# Schema.net
KiCad netlist of a schematic drawn in Altium Designer
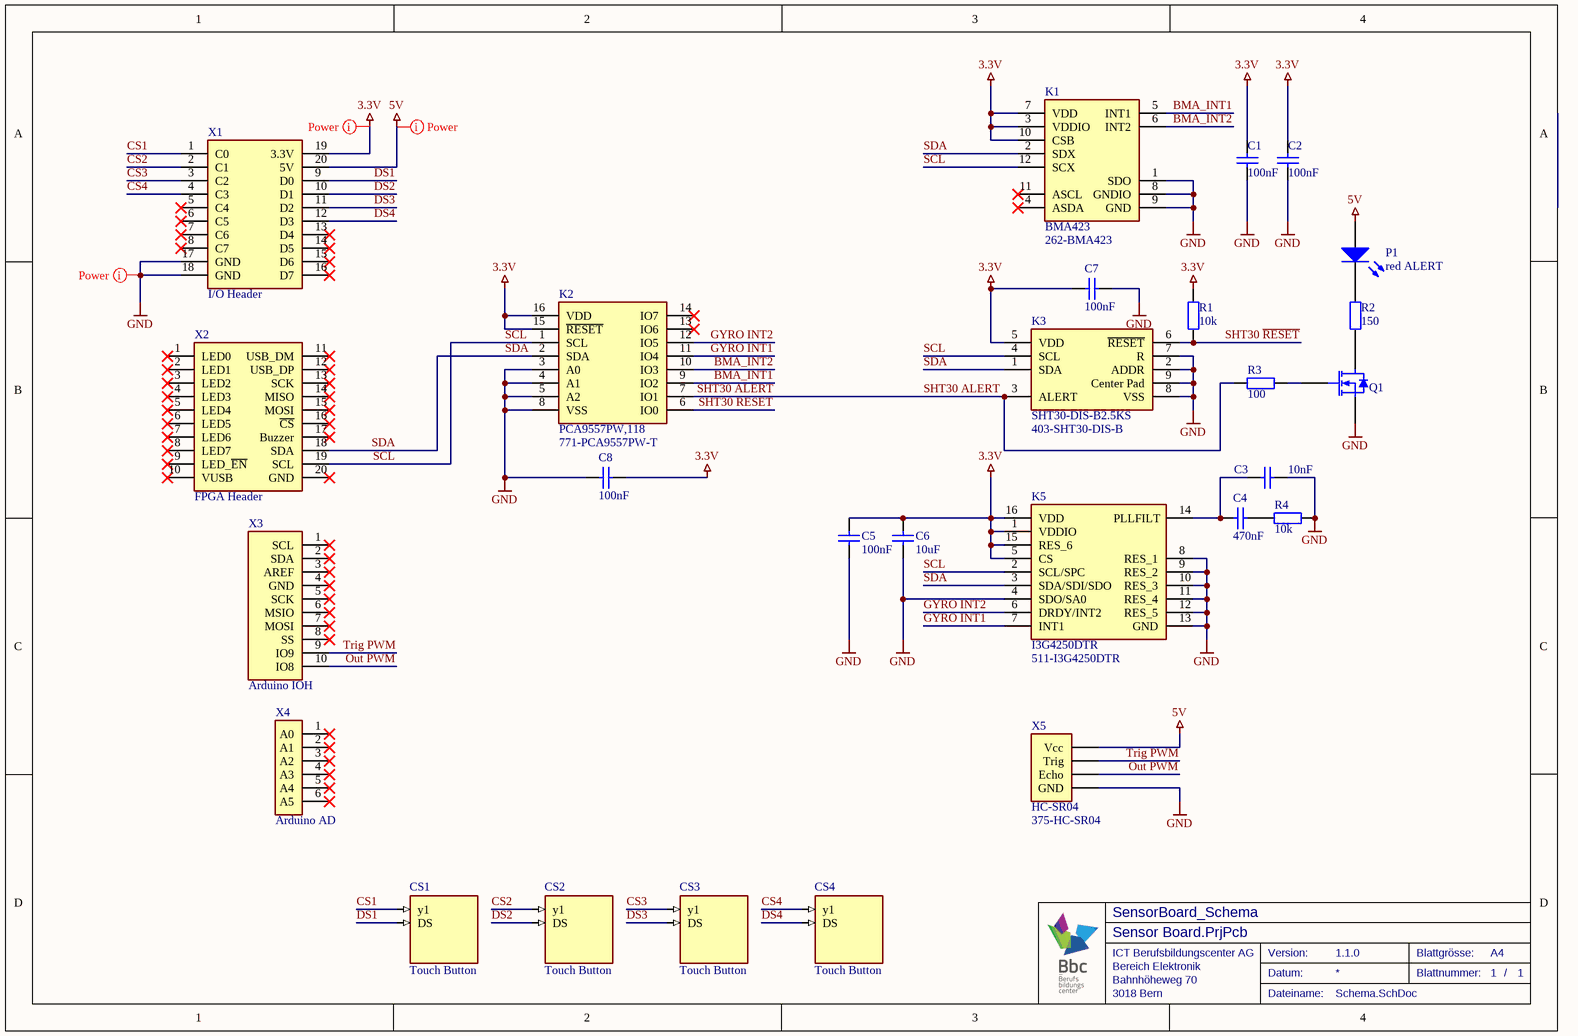
[diagram p0: Schema.SchDoc]

(export (version "E")
  (design (tool "Eeschema 10.0.6"))
  (components
    (comp (ref "C1")
      (value "100nF")
      (footprint "CAP CER 0805 H")
      (description "Non polarized capacitor")
      (fields (field (name "Comment") "Capacitor") (field (name "PUBLISHER") "ICT Berufsbildungscenter AG"))
      (libsource (lib "BBC_Components") (part "Capacitor"))
    )
    (comp (ref "C2")
      (value "100nF")
      (footprint "CAP CER 0805 H")
      (description "Non polarized capacitor")
      (fields (field (name "Comment") "Capacitor") (field (name "PUBLISHER") "ICT Berufsbildungscenter AG"))
      (libsource (lib "BBC_Components") (part "Capacitor"))
    )
    (comp (ref "C3")
      (value "10nF")
      (footprint "CAP CER 0805 H")
      (description "Non polarized capacitor")
      (fields (field (name "Comment") "Capacitor") (field (name "PUBLISHER") "ICT Berufsbildungscenter AG"))
      (libsource (lib "BBC_Components") (part "Capacitor"))
    )
    (comp (ref "C4")
      (value "470nF")
      (footprint "CAP CER 0805 H")
      (description "Non polarized capacitor")
      (fields (field (name "Comment") "Capacitor") (field (name "PUBLISHER") "ICT Berufsbildungscenter AG"))
      (libsource (lib "BBC_Components") (part "Capacitor"))
    )
    (comp (ref "C5")
      (value "100nF")
      (footprint "CAP CER 0805 H")
      (description "Non polarized capacitor")
      (fields (field (name "Comment") "Capacitor") (field (name "PUBLISHER") "ICT Berufsbildungscenter AG"))
      (libsource (lib "BBC_Components") (part "Capacitor"))
    )
    (comp (ref "C6")
      (value "10uF")
      (footprint "CAP CER 0805 H")
      (description "Non polarized capacitor")
      (fields (field (name "Comment") "Capacitor") (field (name "PUBLISHER") "ICT Berufsbildungscenter AG"))
      (libsource (lib "BBC_Components") (part "Capacitor"))
    )
    (comp (ref "C7")
      (value "100nF")
      (footprint "CAP CER 0805 H")
      (description "Non polarized capacitor")
      (fields (field (name "Comment") "Capacitor") (field (name "PUBLISHER") "ICT Berufsbildungscenter AG"))
      (libsource (lib "BBC_Components") (part "Capacitor"))
    )
    (comp (ref "C8")
      (value "100nF")
      (footprint "CAP CER 0805 H")
      (description "Non polarized capacitor")
      (fields (field (name "Comment") "Capacitor") (field (name "PUBLISHER") "ICT Berufsbildungscenter AG"))
      (libsource (lib "BBC_Components") (part "Capacitor"))
    )
    (comp (ref "CS1")
      (value "Touch Button")
      (footprint "Button Self Rectangle")
      (description "Rechteckige Kupferfläche")
      (libsource (lib "SchematicLibrary") (part "Touch Button"))
    )
    (comp (ref "CS2")
      (value "Touch Button")
      (footprint "Button Self Rectangle")
      (description "Rechteckige Kupferfläche")
      (libsource (lib "SchematicLibrary") (part "Touch Button"))
    )
    (comp (ref "CS3")
      (value "Touch Button")
      (footprint "Button Self Rectangle")
      (description "Rechteckige Kupferfläche")
      (libsource (lib "SchematicLibrary") (part "Touch Button"))
    )
    (comp (ref "CS4")
      (value "Touch Button")
      (footprint "Button Self Rectangle")
      (description "Rechteckige Kupferfläche")
      (libsource (lib "SchematicLibrary") (part "Touch Button"))
    )
    (comp (ref "K1")
      (value "BMA423")
      (footprint "Footprints:BMA423")
      (description "Beschleunigungsmesser Triaxial low-g 12bit Acceleration Sensor")
      (fields (field (name "SUPPLIER PART NUMBER 1") "262-BMA423"))
      (libsource (lib "SchematicLibrary") (part "Beschleunigungsmesser"))
    )
    (comp (ref "K2")
      (value "PCA9557PW,118")
      (footprint "Footprints:SOP65P640X110-16N")
      (description "Schnittstelle - I/O-Erweiterer OCT SMBUS/I2C INTRFC")
      (fields (field (name "SUPPLIER PART NUMBER 1") "771-PCA9557PW-T"))
      (libsource (lib "SchematicLibrary") (part "Port Expander"))
    )
    (comp (ref "K3")
      (value "SHT30-DIS-B2.5KS")
      (footprint "Footprints:SHT30DISB25KS")
      (description "Feuchtigkeitssensoren für Plattenmontage RH Accuracy +/- 3% Digital, DFN Type")
      (fields (field (name "SUPPLIER PART NUMBER 1") "403-SHT30-DIS-B"))
      (libsource (lib "SchematicLibrary") (part "Humidity & Temp. Sensor"))
    )
    (comp (ref "K5")
      (value "I3G4250DTR")
      (footprint "Footprints:LGA-16L(4X4X1.1MM)")
      (description "Gyroskope AUTO & INDUSTRIAL SENSORS")
      (fields (field (name "SUPPLIER PART NUMBER 1") "511-I3G4250DTR"))
      (libsource (lib "SchematicLibrary") (part "Gyroskop"))
    )
    (comp (ref "P1")
      (value "red ALERT")
      (footprint "LED 1206 red H")
      (description "Light emitting diode")
      (fields (field (name "PUBLISHER") "ICT Berufsbildungscenter AG"))
      (libsource (lib "BBC_Components") (part "LED"))
    )
    (comp (ref "Q1")
      (value "MOSFET N-Channel")
      (footprint "SOT96P237X111-3N")
      (libsource (lib "SchematicLibrary") (part "MOSFET N-Channel"))
    )
    (comp (ref "R1")
      (value "10k")
      (footprint "RES 0805 H")
      (description "Resistor")
      (fields (field (name "PUBLISHER") "ICT Berufsbildungscenter AG"))
      (libsource (lib "") (part "Resistor_1"))
    )
    (comp (ref "R2")
      (value "150")
      (footprint "RES 0805 H")
      (description "Resistor")
      (fields (field (name "PUBLISHER") "ICT Berufsbildungscenter AG"))
      (libsource (lib "") (part "Resistor_1"))
    )
    (comp (ref "R3")
      (value "100")
      (footprint "RES 0805 H")
      (description "Resistor")
      (fields (field (name "PUBLISHER") "ICT Berufsbildungscenter AG"))
      (libsource (lib "BBC_Components") (part "Resistor"))
    )
    (comp (ref "R4")
      (value "10k")
      (footprint "RES 0805 H")
      (description "Resistor")
      (fields (field (name "PUBLISHER") "ICT Berufsbildungscenter AG"))
      (libsource (lib "BBC_Components") (part "Resistor"))
    )
    (comp (ref "X1")
      (value "I/O Header")
      (footprint "Header THT male 2x10")
      (description "board to board header")
      (fields (field (name "PUBLISHER") "ICT Berufsbildungscenter AG"))
      (libsource (lib "SchematicLibrary") (part "I/O Header"))
    )
    (comp (ref "X2")
      (value "FPGA Header")
      (footprint "Header THT male 2x10")
      (description "board to board header")
      (fields (field (name "PUBLISHER") "ICT Berufsbildungscenter AG"))
      (libsource (lib "SchematicLibrary") (part "FPGA Header"))
    )
    (comp (ref "X3")
      (value "Arduino IOH")
      (footprint "Header THT male 1x10")
      (description "board to board header")
      (fields (field (name "PUBLISHER") "ICT Berufsbildungscenter AG"))
      (libsource (lib "SchematicLibrary") (part "Arduino IOH"))
    )
    (comp (ref "X4")
      (value "Arduino AD")
      (footprint "Header THT male 1x6")
      (description "board to board header")
      (fields (field (name "PUBLISHER") "ICT Berufsbildungscenter AG"))
      (libsource (lib "SchematicLibrary") (part "Arduino AD"))
    )
    (comp (ref "X5")
      (value "HC-SR04")
      (footprint "HC-SR04")
      (description "Buchsenanschluss für den Sensor")
      (fields (field (name "SUPPLIER PART NUMBER 1") "375-HC-SR04"))
      (libsource (lib "SchematicLibrary") (part "Ultraschall-Distanzsensor"))
    )
  )
  (nets
    (net (code "1") (name "/BMA_INT1") (class "Default")
      (node (ref "K1") (pin "5") (pinfunction "INT1_5") (pintype "passive"))
      (node (ref "K2") (pin "9") (pinfunction "IO2_9") (pintype "passive"))
    )
    (net (code "2") (name "/BMA_INT2") (class "Default")
      (node (ref "K1") (pin "6") (pinfunction "INT2_6") (pintype "passive"))
      (node (ref "K2") (pin "10") (pinfunction "IO3_10") (pintype "passive"))
    )
    (net (code "3") (name "/CS1") (class "Default")
      (node (ref "CS1") (pin "y1") (pinfunction "y1_y1") (pintype "input"))
      (node (ref "X1") (pin "1") (pinfunction "C0_1") (pintype "passive"))
    )
    (net (code "4") (name "/CS2") (class "Default")
      (node (ref "CS2") (pin "y1") (pinfunction "y1_y1") (pintype "input"))
      (node (ref "X1") (pin "2") (pinfunction "C1_2") (pintype "passive"))
    )
    (net (code "5") (name "/CS3") (class "Default")
      (node (ref "CS3") (pin "y1") (pinfunction "y1_y1") (pintype "input"))
      (node (ref "X1") (pin "3") (pinfunction "C2_3") (pintype "passive"))
    )
    (net (code "6") (name "/CS4") (class "Default")
      (node (ref "CS4") (pin "y1") (pinfunction "y1_y1") (pintype "input"))
      (node (ref "X1") (pin "4") (pinfunction "C3_4") (pintype "passive"))
    )
    (net (code "7") (name "/DS1") (class "Default")
      (node (ref "CS1") (pin "DS") (pinfunction "DS_DS") (pintype "input"))
      (node (ref "X1") (pin "9") (pinfunction "D0_9") (pintype "passive"))
    )
    (net (code "8") (name "/DS2") (class "Default")
      (node (ref "CS2") (pin "DS") (pinfunction "DS_DS") (pintype "input"))
      (node (ref "X1") (pin "10") (pinfunction "D1_10") (pintype "passive"))
    )
    (net (code "9") (name "/DS3") (class "Default")
      (node (ref "CS3") (pin "DS") (pinfunction "DS_DS") (pintype "input"))
      (node (ref "X1") (pin "11") (pinfunction "D2_11") (pintype "passive"))
    )
    (net (code "10") (name "/DS4") (class "Default")
      (node (ref "CS4") (pin "DS") (pinfunction "DS_DS") (pintype "input"))
      (node (ref "X1") (pin "12") (pinfunction "D3_12") (pintype "passive"))
    )
    (net (code "11") (name "/GYRO INT1") (class "Default")
      (node (ref "K2") (pin "11") (pinfunction "IO4_11") (pintype "passive"))
      (node (ref "K5") (pin "7") (pinfunction "INT1_7") (pintype "passive"))
    )
    (net (code "12") (name "/GYRO INT2") (class "Default")
      (node (ref "K2") (pin "12") (pinfunction "IO5_12") (pintype "passive"))
      (node (ref "K5") (pin "6") (pinfunction "DRDY/INT2_6") (pintype "passive"))
    )
    (net (code "13") (name "/Out PWM") (class "Default")
      (node (ref "X3") (pin "10") (pinfunction "IO8_10") (pintype "passive"))
      (node (ref "X5") (pin "3") (pinfunction "Echo_3") (pintype "passive"))
    )
    (net (code "14") (name "/SCL") (class "Default")
      (node (ref "K1") (pin "12") (pinfunction "SCX_12") (pintype "passive"))
      (node (ref "K2") (pin "1") (pinfunction "SCL_1") (pintype "passive"))
      (node (ref "K3") (pin "4") (pinfunction "SCL_4") (pintype "passive"))
      (node (ref "K5") (pin "2") (pinfunction "SCL/SPC_2") (pintype "passive"))
      (node (ref "X2") (pin "19") (pinfunction "SCL_19") (pintype "passive"))
    )
    (net (code "15") (name "/SDA") (class "Default")
      (node (ref "K1") (pin "2") (pinfunction "SDX_2") (pintype "passive"))
      (node (ref "K2") (pin "2") (pinfunction "SDA_2") (pintype "passive"))
      (node (ref "K3") (pin "1") (pinfunction "SDA_1") (pintype "passive"))
      (node (ref "K5") (pin "3") (pinfunction "SDA/SDI/SDO_3") (pintype "passive"))
      (node (ref "X2") (pin "18") (pinfunction "SDA_18") (pintype "passive"))
    )
    (net (code "16") (name "/SHT30 ALERT") (class "Default")
      (node (ref "K2") (pin "7") (pinfunction "IO1_7") (pintype "passive"))
      (node (ref "K3") (pin "3") (pinfunction "ALERT_3") (pintype "passive"))
      (node (ref "R3") (pin "1") (pinfunction "1_1") (pintype "passive"))
    )
    (net (code "17") (name "/SHT30 ~{RESET}") (class "Default")
      (node (ref "K2") (pin "6") (pinfunction "IO0_6") (pintype "passive"))
      (node (ref "K3") (pin "6") (pinfunction "~{RESET}_6") (pintype "passive"))
      (node (ref "R1") (pin "1") (pinfunction "1_1") (pintype "passive"))
    )
    (net (code "18") (name "/Trig PWM") (class "Default")
      (node (ref "X3") (pin "9") (pinfunction "IO9_9") (pintype "passive"))
      (node (ref "X5") (pin "2") (pinfunction "Trig_2") (pintype "passive"))
    )
    (net (code "19") (name "3.3V") (class "Default")
      (node (ref "C1") (pin "2") (pinfunction "2_2") (pintype "passive"))
      (node (ref "C2") (pin "1") (pinfunction "1_1") (pintype "passive"))
      (node (ref "C5") (pin "1") (pinfunction "1_1") (pintype "passive"))
      (node (ref "C6") (pin "1") (pinfunction "1_1") (pintype "passive"))
      (node (ref "C7") (pin "1") (pinfunction "1_1") (pintype "passive"))
      (node (ref "C8") (pin "2") (pinfunction "2_2") (pintype "passive"))
      (node (ref "K1") (pin "10") (pinfunction "CSB_10") (pintype "passive"))
      (node (ref "K1") (pin "3") (pinfunction "VDDIO_3") (pintype "passive"))
      (node (ref "K1") (pin "7") (pinfunction "VDD_7") (pintype "passive"))
      (node (ref "K2") (pin "15") (pinfunction "~{RESET}_15") (pintype "passive"))
      (node (ref "K2") (pin "16") (pinfunction "VDD_16") (pintype "passive"))
      (node (ref "K3") (pin "5") (pinfunction "VDD_5") (pintype "passive"))
      (node (ref "K5") (pin "1") (pinfunction "VDDIO_1") (pintype "passive"))
      (node (ref "K5") (pin "15") (pinfunction "RES_6_15") (pintype "passive"))
      (node (ref "K5") (pin "16") (pinfunction "VDD_16") (pintype "passive"))
      (node (ref "K5") (pin "5") (pinfunction "CS_5") (pintype "passive"))
      (node (ref "R1") (pin "2") (pinfunction "2_2") (pintype "passive"))
      (node (ref "X1") (pin "19") (pinfunction "3.3V_19") (pintype "passive"))
    )
    (net (code "20") (name "5V") (class "Default")
      (node (ref "P1") (pin "A") (pinfunction "Anode_A") (pintype "passive"))
      (node (ref "X1") (pin "20") (pinfunction "5V_20") (pintype "passive"))
      (node (ref "X5") (pin "1") (pinfunction "Vcc_1") (pintype "passive"))
    )
    (net (code "21") (name "GND") (class "Default")
      (node (ref "C1") (pin "1") (pinfunction "1_1") (pintype "passive"))
      (node (ref "C2") (pin "2") (pinfunction "2_2") (pintype "passive"))
      (node (ref "C3") (pin "2") (pinfunction "2_2") (pintype "passive"))
      (node (ref "C5") (pin "2") (pinfunction "2_2") (pintype "passive"))
      (node (ref "C6") (pin "2") (pinfunction "2_2") (pintype "passive"))
      (node (ref "C7") (pin "2") (pinfunction "2_2") (pintype "passive"))
      (node (ref "C8") (pin "1") (pinfunction "1_1") (pintype "passive"))
      (node (ref "K1") (pin "1") (pinfunction "SDO_1") (pintype "passive"))
      (node (ref "K1") (pin "8") (pinfunction "GNDIO_8") (pintype "passive"))
      (node (ref "K1") (pin "9") (pinfunction "GND_9") (pintype "passive"))
      (node (ref "K2") (pin "3") (pinfunction "A0_3") (pintype "passive"))
      (node (ref "K2") (pin "4") (pinfunction "A1_4") (pintype "passive"))
      (node (ref "K2") (pin "5") (pinfunction "A2_5") (pintype "passive"))
      (node (ref "K2") (pin "8") (pinfunction "VSS_8") (pintype "passive"))
      (node (ref "K3") (pin "2") (pinfunction "ADDR_2") (pintype "passive"))
      (node (ref "K3") (pin "7") (pinfunction "R_7") (pintype "passive"))
      (node (ref "K3") (pin "8") (pinfunction "VSS_8") (pintype "passive"))
      (node (ref "K3") (pin "9") (pinfunction "Center_Pad_9") (pintype "passive"))
      (node (ref "K5") (pin "10") (pinfunction "RES_3_10") (pintype "passive"))
      (node (ref "K5") (pin "11") (pinfunction "RES_4_11") (pintype "passive"))
      (node (ref "K5") (pin "12") (pinfunction "RES_5_12") (pintype "passive"))
      (node (ref "K5") (pin "13") (pinfunction "GND_13") (pintype "passive"))
      (node (ref "K5") (pin "4") (pinfunction "SDO/SA0_4") (pintype "passive"))
      (node (ref "K5") (pin "8") (pinfunction "RES_1_8") (pintype "passive"))
      (node (ref "K5") (pin "9") (pinfunction "RES_2_9") (pintype "passive"))
      (node (ref "Q1") (pin "2") (pinfunction "S_2") (pintype "passive"))
      (node (ref "R4") (pin "2") (pinfunction "2_2") (pintype "passive"))
      (node (ref "X1") (pin "17") (pinfunction "GND_17") (pintype "passive"))
      (node (ref "X1") (pin "18") (pinfunction "GND_18") (pintype "passive"))
      (node (ref "X5") (pin "4") (pinfunction "GND_4") (pintype "passive"))
    )
    (net (code "22") (name "Net-(C4-Pad2)") (class "Default")
      (node (ref "C4") (pin "2") (pinfunction "2_2") (pintype "passive"))
      (node (ref "R4") (pin "1") (pinfunction "1_1") (pintype "passive"))
    )
    (net (code "23") (name "Net-(K5-PLLFILT)") (class "Default")
      (node (ref "C3") (pin "1") (pinfunction "1_1") (pintype "passive"))
      (node (ref "C4") (pin "1") (pinfunction "1_1") (pintype "passive"))
      (node (ref "K5") (pin "14") (pinfunction "PLLFILT_14") (pintype "passive"))
    )
    (net (code "24") (name "Net-(P1-Cathode)") (class "Default")
      (node (ref "P1") (pin "C") (pinfunction "Cathode_C") (pintype "passive"))
      (node (ref "R2") (pin "2") (pinfunction "2_2") (pintype "passive"))
    )
    (net (code "25") (name "Net-(Q1-D)") (class "Default")
      (node (ref "Q1") (pin "3") (pinfunction "D_3") (pintype "passive"))
      (node (ref "R2") (pin "1") (pinfunction "1_1") (pintype "passive"))
    )
    (net (code "26") (name "Net-(Q1-G)") (class "Default")
      (node (ref "Q1") (pin "1") (pinfunction "G_1") (pintype "passive"))
      (node (ref "R3") (pin "2") (pinfunction "2_2") (pintype "passive"))
    )
    (net (code "27") (name "unconnected-(K1-ASCL-Pad11)") (class "Default")
      (node (ref "K1") (pin "11") (pinfunction "ASCL_11") (pintype "passive+no_connect"))
    )
    (net (code "28") (name "unconnected-(K1-ASDA-Pad4)") (class "Default")
      (node (ref "K1") (pin "4") (pinfunction "ASDA_4") (pintype "passive+no_connect"))
    )
    (net (code "29") (name "unconnected-(K2-IO6-Pad13)") (class "Default")
      (node (ref "K2") (pin "13") (pinfunction "IO6_13") (pintype "passive+no_connect"))
    )
    (net (code "30") (name "unconnected-(K2-IO7-Pad14)") (class "Default")
      (node (ref "K2") (pin "14") (pinfunction "IO7_14") (pintype "passive+no_connect"))
    )
    (net (code "31") (name "unconnected-(X1-C4-Pad5)") (class "Default")
      (node (ref "X1") (pin "5") (pinfunction "C4_5") (pintype "passive+no_connect"))
    )
    (net (code "32") (name "unconnected-(X1-C5-Pad6)") (class "Default")
      (node (ref "X1") (pin "6") (pinfunction "C5_6") (pintype "passive+no_connect"))
    )
    (net (code "33") (name "unconnected-(X1-C6-Pad7)") (class "Default")
      (node (ref "X1") (pin "7") (pinfunction "C6_7") (pintype "passive+no_connect"))
    )
    (net (code "34") (name "unconnected-(X1-C7-Pad8)") (class "Default")
      (node (ref "X1") (pin "8") (pinfunction "C7_8") (pintype "passive+no_connect"))
    )
    (net (code "35") (name "unconnected-(X1-D4-Pad13)") (class "Default")
      (node (ref "X1") (pin "13") (pinfunction "D4_13") (pintype "passive+no_connect"))
    )
    (net (code "36") (name "unconnected-(X1-D5-Pad14)") (class "Default")
      (node (ref "X1") (pin "14") (pinfunction "D5_14") (pintype "passive+no_connect"))
    )
    (net (code "37") (name "unconnected-(X1-D6-Pad15)") (class "Default")
      (node (ref "X1") (pin "15") (pinfunction "D6_15") (pintype "passive+no_connect"))
    )
    (net (code "38") (name "unconnected-(X1-D7-Pad16)") (class "Default")
      (node (ref "X1") (pin "16") (pinfunction "D7_16") (pintype "passive+no_connect"))
    )
    (net (code "39") (name "unconnected-(X2-Buzzer-Pad17)") (class "Default")
      (node (ref "X2") (pin "17") (pinfunction "Buzzer_17") (pintype "passive+no_connect"))
    )
    (net (code "40") (name "unconnected-(X2-GND-Pad20)") (class "Default")
      (node (ref "X2") (pin "20") (pinfunction "GND_20") (pintype "passive+no_connect"))
    )
    (net (code "41") (name "unconnected-(X2-LED0-Pad1)") (class "Default")
      (node (ref "X2") (pin "1") (pinfunction "LED0_1") (pintype "passive+no_connect"))
    )
    (net (code "42") (name "unconnected-(X2-LED1-Pad2)") (class "Default")
      (node (ref "X2") (pin "2") (pinfunction "LED1_2") (pintype "passive+no_connect"))
    )
    (net (code "43") (name "unconnected-(X2-LED2-Pad3)") (class "Default")
      (node (ref "X2") (pin "3") (pinfunction "LED2_3") (pintype "passive+no_connect"))
    )
    (net (code "44") (name "unconnected-(X2-LED3-Pad4)") (class "Default")
      (node (ref "X2") (pin "4") (pinfunction "LED3_4") (pintype "passive+no_connect"))
    )
    (net (code "45") (name "unconnected-(X2-LED4-Pad5)") (class "Default")
      (node (ref "X2") (pin "5") (pinfunction "LED4_5") (pintype "passive+no_connect"))
    )
    (net (code "46") (name "unconnected-(X2-LED5-Pad6)") (class "Default")
      (node (ref "X2") (pin "6") (pinfunction "LED5_6") (pintype "passive+no_connect"))
    )
    (net (code "47") (name "unconnected-(X2-LED6-Pad7)") (class "Default")
      (node (ref "X2") (pin "7") (pinfunction "LED6_7") (pintype "passive+no_connect"))
    )
    (net (code "48") (name "unconnected-(X2-LED7-Pad8)") (class "Default")
      (node (ref "X2") (pin "8") (pinfunction "LED7_8") (pintype "passive+no_connect"))
    )
    (net (code "49") (name "unconnected-(X2-LED_~{EN}-Pad9)") (class "Default")
      (node (ref "X2") (pin "9") (pinfunction "LED_~{EN}_9") (pintype "passive+no_connect"))
    )
    (net (code "50") (name "unconnected-(X2-MISO-Pad14)") (class "Default")
      (node (ref "X2") (pin "14") (pinfunction "MISO_14") (pintype "passive+no_connect"))
    )
    (net (code "51") (name "unconnected-(X2-MOSI-Pad15)") (class "Default")
      (node (ref "X2") (pin "15") (pinfunction "MOSI_15") (pintype "passive+no_connect"))
    )
    (net (code "52") (name "unconnected-(X2-SCK-Pad13)") (class "Default")
      (node (ref "X2") (pin "13") (pinfunction "SCK_13") (pintype "passive+no_connect"))
    )
    (net (code "53") (name "unconnected-(X2-USB_DM-Pad11)") (class "Default")
      (node (ref "X2") (pin "11") (pinfunction "USB_DM_11") (pintype "passive+no_connect"))
    )
    (net (code "54") (name "unconnected-(X2-USB_DP-Pad12)") (class "Default")
      (node (ref "X2") (pin "12") (pinfunction "USB_DP_12") (pintype "passive+no_connect"))
    )
    (net (code "55") (name "unconnected-(X2-VUSB-Pad10)") (class "Default")
      (node (ref "X2") (pin "10") (pinfunction "VUSB_10") (pintype "passive+no_connect"))
    )
    (net (code "56") (name "unconnected-(X2-~{CS}-Pad16)") (class "Default")
      (node (ref "X2") (pin "16") (pinfunction "~{CS}_16") (pintype "passive+no_connect"))
    )
    (net (code "57") (name "unconnected-(X3-AREF-Pad3)") (class "Default")
      (node (ref "X3") (pin "3") (pinfunction "AREF_3") (pintype "passive+no_connect"))
    )
    (net (code "58") (name "unconnected-(X3-GND-Pad4)") (class "Default")
      (node (ref "X3") (pin "4") (pinfunction "GND_4") (pintype "passive+no_connect"))
    )
    (net (code "59") (name "unconnected-(X3-MOSI-Pad7)") (class "Default")
      (node (ref "X3") (pin "7") (pinfunction "MOSI_7") (pintype "passive+no_connect"))
    )
    (net (code "60") (name "unconnected-(X3-MSIO-Pad6)") (class "Default")
      (node (ref "X3") (pin "6") (pinfunction "MSIO_6") (pintype "passive+no_connect"))
    )
    (net (code "61") (name "unconnected-(X3-SCK-Pad5)") (class "Default")
      (node (ref "X3") (pin "5") (pinfunction "SCK_5") (pintype "passive+no_connect"))
    )
    (net (code "62") (name "unconnected-(X3-SCL-Pad1)") (class "Default")
      (node (ref "X3") (pin "1") (pinfunction "SCL_1") (pintype "passive+no_connect"))
    )
    (net (code "63") (name "unconnected-(X3-SDA-Pad2)") (class "Default")
      (node (ref "X3") (pin "2") (pinfunction "SDA_2") (pintype "passive+no_connect"))
    )
    (net (code "64") (name "unconnected-(X3-SS-Pad8)") (class "Default")
      (node (ref "X3") (pin "8") (pinfunction "SS_8") (pintype "passive+no_connect"))
    )
    (net (code "65") (name "unconnected-(X4-A0-Pad1)") (class "Default")
      (node (ref "X4") (pin "1") (pinfunction "A0_1") (pintype "passive+no_connect"))
    )
    (net (code "66") (name "unconnected-(X4-A1-Pad2)") (class "Default")
      (node (ref "X4") (pin "2") (pinfunction "A1_2") (pintype "passive+no_connect"))
    )
    (net (code "67") (name "unconnected-(X4-A2-Pad3)") (class "Default")
      (node (ref "X4") (pin "3") (pinfunction "A2_3") (pintype "passive+no_connect"))
    )
    (net (code "68") (name "unconnected-(X4-A3-Pad4)") (class "Default")
      (node (ref "X4") (pin "4") (pinfunction "A3_4") (pintype "passive+no_connect"))
    )
    (net (code "69") (name "unconnected-(X4-A4-Pad5)") (class "Default")
      (node (ref "X4") (pin "5") (pinfunction "A4_5") (pintype "passive+no_connect"))
    )
    (net (code "70") (name "unconnected-(X4-A5-Pad6)") (class "Default")
      (node (ref "X4") (pin "6") (pinfunction "A5_6") (pintype "passive+no_connect"))
    )
  )
)
